# dv_spectrum_col.net
KiCad netlist of a schematic drawn in Altium Designer
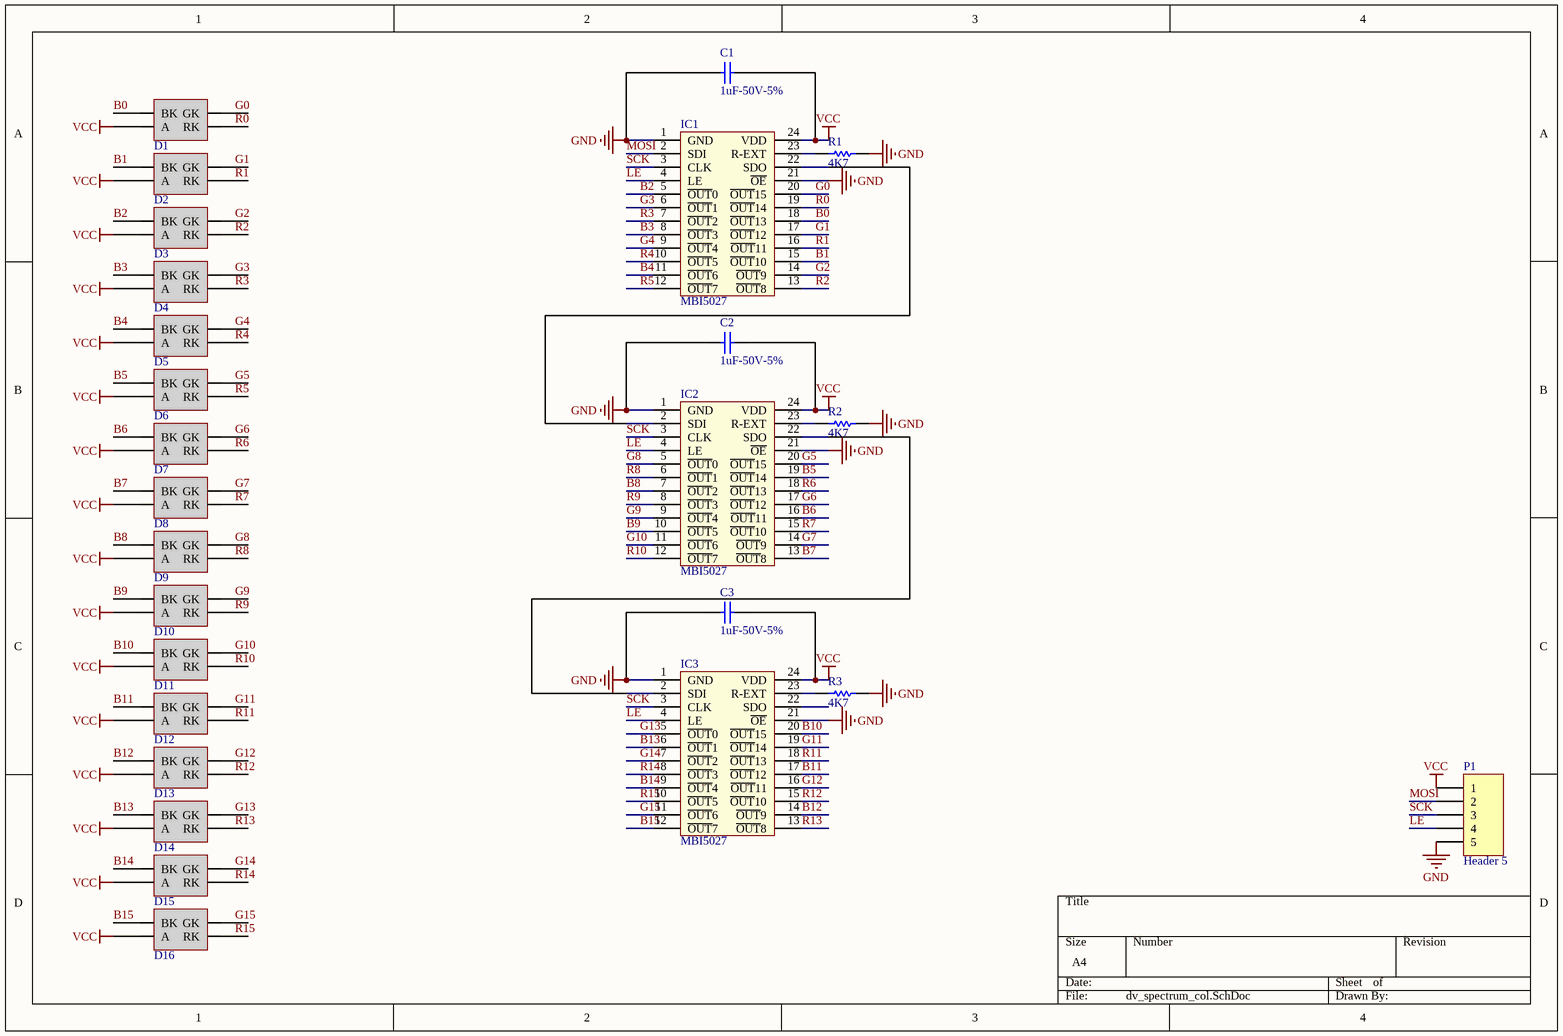
[diagram p0: dv_spectrum_col.SchDoc]

(export (version "E")
  (design (tool "Eeschema 10.0.6"))
  (components
    (comp (ref "C1")
      (value "1uF-50V-5%")
      (footprint "CAPC2012X135N")
      (description "CAP CER 15PF 50V 5% NPO 0603")
      (fields
        (field (name "MANUFACTURER") "Yageo")
        (field (name "DIGI-KEY PART NUMBER") "311-1060-1-ND")
        (field (name "PUBLISHER") "Altium Limited")
      )
      (libsource (lib "altium-import") (part "root_0_Cap_"))
    )
    (comp (ref "C2")
      (value "1uF-50V-5%")
      (footprint "CAPC2012X135N")
      (description "CAP CER 15PF 50V 5% NPO 0603")
      (fields
        (field (name "MANUFACTURER") "Yageo")
        (field (name "DIGI-KEY PART NUMBER") "311-1060-1-ND")
        (field (name "PUBLISHER") "Altium Limited")
      )
      (libsource (lib "altium-import") (part "root_0_Cap_"))
    )
    (comp (ref "C3")
      (value "1uF-50V-5%")
      (footprint "CAPC2012X135N")
      (description "CAP CER 15PF 50V 5% NPO 0603")
      (fields
        (field (name "MANUFACTURER") "Yageo")
        (field (name "DIGI-KEY PART NUMBER") "311-1060-1-ND")
        (field (name "PUBLISHER") "Altium Limited")
      )
      (libsource (lib "altium-import") (part "root_0_Cap_"))
    )
    (comp (ref "D1")
      (value "LED_RGB")
      (footprint "LED3528(1210)-RGB")
      (libsource (lib "PBL - Light Sources") (part "LED_RGB_1210"))
    )
    (comp (ref "D2")
      (value "LED_RGB")
      (footprint "LED3528(1210)-RGB")
      (libsource (lib "PBL - Light Sources") (part "LED_RGB_1210"))
    )
    (comp (ref "D3")
      (value "LED_RGB")
      (footprint "LED3528(1210)-RGB")
      (libsource (lib "PBL - Light Sources") (part "LED_RGB_1210"))
    )
    (comp (ref "D4")
      (value "LED_RGB")
      (footprint "LED3528(1210)-RGB")
      (libsource (lib "PBL - Light Sources") (part "LED_RGB_1210"))
    )
    (comp (ref "D5")
      (value "LED_RGB")
      (footprint "LED3528(1210)-RGB")
      (libsource (lib "PBL - Light Sources") (part "LED_RGB_1210"))
    )
    (comp (ref "D6")
      (value "LED_RGB")
      (footprint "LED3528(1210)-RGB")
      (libsource (lib "PBL - Light Sources") (part "LED_RGB_1210"))
    )
    (comp (ref "D7")
      (value "LED_RGB")
      (footprint "LED3528(1210)-RGB")
      (libsource (lib "PBL - Light Sources") (part "LED_RGB_1210"))
    )
    (comp (ref "D8")
      (value "LED_RGB")
      (footprint "LED3528(1210)-RGB")
      (libsource (lib "PBL - Light Sources") (part "LED_RGB_1210"))
    )
    (comp (ref "D9")
      (value "LED_RGB")
      (footprint "LED3528(1210)-RGB")
      (libsource (lib "PBL - Light Sources") (part "LED_RGB_1210"))
    )
    (comp (ref "D10")
      (value "LED_RGB")
      (footprint "LED3528(1210)-RGB")
      (libsource (lib "PBL - Light Sources") (part "LED_RGB_1210"))
    )
    (comp (ref "D11")
      (value "LED_RGB")
      (footprint "LED3528(1210)-RGB")
      (libsource (lib "PBL - Light Sources") (part "LED_RGB_1210"))
    )
    (comp (ref "D12")
      (value "LED_RGB")
      (footprint "LED3528(1210)-RGB")
      (libsource (lib "PBL - Light Sources") (part "LED_RGB_1210"))
    )
    (comp (ref "D13")
      (value "LED_RGB")
      (footprint "LED3528(1210)-RGB")
      (libsource (lib "PBL - Light Sources") (part "LED_RGB_1210"))
    )
    (comp (ref "D14")
      (value "LED_RGB")
      (footprint "LED3528(1210)-RGB")
      (libsource (lib "PBL - Light Sources") (part "LED_RGB_1210"))
    )
    (comp (ref "D15")
      (value "LED_RGB")
      (footprint "LED3528(1210)-RGB")
      (libsource (lib "PBL - Light Sources") (part "LED_RGB_1210"))
    )
    (comp (ref "D16")
      (value "LED_RGB")
      (footprint "LED3528(1210)-RGB")
      (libsource (lib "PBL - Light Sources") (part "LED_RGB_1210"))
    )
    (comp (ref "IC1")
      (value "MBI5027")
      (footprint "SSOP24")
      (description "16 bit Constant Current LED")
      (fields (field (name "CREAT BY") "VanDungEvn@Gmail.com"))
      (libsource (lib "syhaunguyen") (part "MBI5027"))
    )
    (comp (ref "IC2")
      (value "MBI5027")
      (footprint "SSOP24")
      (description "16 bit Constant Current LED")
      (fields (field (name "CREAT BY") "VanDungEvn@Gmail.com"))
      (libsource (lib "syhaunguyen") (part "MBI5027"))
    )
    (comp (ref "IC3")
      (value "MBI5027")
      (footprint "SSOP24")
      (description "16 bit Constant Current LED")
      (fields (field (name "CREAT BY") "VanDungEvn@Gmail.com"))
      (libsource (lib "syhaunguyen") (part "MBI5027"))
    )
    (comp (ref "P1")
      (value "Header 5")
      (footprint "HDR1X5")
      (description "Header, 5-Pin")
      (fields (field (name "PUBLISHER") "Altium Limited"))
      (libsource (lib "Miscellaneous Connectors") (part "Header 5"))
    )
    (comp (ref "R1")
      (value "4K7")
      (footprint "R0805")
      (description "Resistor")
      (fields (field (name "Comment") "Res1") (field (name "PUBLISHER") "Altium Limited"))
      (libsource (lib "Miscellaneous Devices") (part "Res1"))
    )
    (comp (ref "R2")
      (value "4K7")
      (footprint "R0805")
      (description "Resistor")
      (fields (field (name "Comment") "Res1") (field (name "PUBLISHER") "Altium Limited"))
      (libsource (lib "Miscellaneous Devices") (part "Res1"))
    )
    (comp (ref "R3")
      (value "4K7")
      (footprint "R0805")
      (description "Resistor")
      (fields (field (name "Comment") "Res1") (field (name "PUBLISHER") "Altium Limited"))
      (libsource (lib "Miscellaneous Devices") (part "Res1"))
    )
  )
  (nets
    (net (code "1") (name "/B0") (class "Default")
      (node (ref "D1") (pin "3") (pinfunction "BK_3") (pintype "passive"))
      (node (ref "IC1") (pin "18") (pinfunction "~{OUT}13_18") (pintype "passive"))
    )
    (net (code "2") (name "/B1") (class "Default")
      (node (ref "D2") (pin "3") (pinfunction "BK_3") (pintype "passive"))
      (node (ref "IC1") (pin "15") (pinfunction "~{OUT}10_15") (pintype "passive"))
    )
    (net (code "3") (name "/B2") (class "Default")
      (node (ref "D3") (pin "3") (pinfunction "BK_3") (pintype "passive"))
      (node (ref "IC1") (pin "5") (pinfunction "~{OUT}0_5") (pintype "passive"))
    )
    (net (code "4") (name "/B3") (class "Default")
      (node (ref "D4") (pin "3") (pinfunction "BK_3") (pintype "passive"))
      (node (ref "IC1") (pin "8") (pinfunction "~{OUT}3_8") (pintype "passive"))
    )
    (net (code "5") (name "/B4") (class "Default")
      (node (ref "D5") (pin "3") (pinfunction "BK_3") (pintype "passive"))
      (node (ref "IC1") (pin "11") (pinfunction "~{OUT}6_11") (pintype "passive"))
    )
    (net (code "6") (name "/B5") (class "Default")
      (node (ref "D6") (pin "3") (pinfunction "BK_3") (pintype "passive"))
      (node (ref "IC2") (pin "19") (pinfunction "~{OUT}14_19") (pintype "passive"))
    )
    (net (code "7") (name "/B6") (class "Default")
      (node (ref "D7") (pin "3") (pinfunction "BK_3") (pintype "passive"))
      (node (ref "IC2") (pin "16") (pinfunction "~{OUT}11_16") (pintype "passive"))
    )
    (net (code "8") (name "/B7") (class "Default")
      (node (ref "D8") (pin "3") (pinfunction "BK_3") (pintype "passive"))
      (node (ref "IC2") (pin "13") (pinfunction "~{OUT}8_13") (pintype "passive"))
    )
    (net (code "9") (name "/B8") (class "Default")
      (node (ref "D9") (pin "3") (pinfunction "BK_3") (pintype "passive"))
      (node (ref "IC2") (pin "7") (pinfunction "~{OUT}2_7") (pintype "passive"))
    )
    (net (code "10") (name "/B9") (class "Default")
      (node (ref "D10") (pin "3") (pinfunction "BK_3") (pintype "passive"))
      (node (ref "IC2") (pin "10") (pinfunction "~{OUT}5_10") (pintype "passive"))
    )
    (net (code "11") (name "/B10") (class "Default")
      (node (ref "D11") (pin "3") (pinfunction "BK_3") (pintype "passive"))
      (node (ref "IC3") (pin "20") (pinfunction "~{OUT}15_20") (pintype "passive"))
    )
    (net (code "12") (name "/B11") (class "Default")
      (node (ref "D12") (pin "3") (pinfunction "BK_3") (pintype "passive"))
      (node (ref "IC3") (pin "17") (pinfunction "~{OUT}12_17") (pintype "passive"))
    )
    (net (code "13") (name "/B12") (class "Default")
      (node (ref "D13") (pin "3") (pinfunction "BK_3") (pintype "passive"))
      (node (ref "IC3") (pin "14") (pinfunction "~{OUT}9_14") (pintype "passive"))
    )
    (net (code "14") (name "/B13") (class "Default")
      (node (ref "D14") (pin "3") (pinfunction "BK_3") (pintype "passive"))
      (node (ref "IC3") (pin "6") (pinfunction "~{OUT}1_6") (pintype "passive"))
    )
    (net (code "15") (name "/B14") (class "Default")
      (node (ref "D15") (pin "3") (pinfunction "BK_3") (pintype "passive"))
      (node (ref "IC3") (pin "9") (pinfunction "~{OUT}4_9") (pintype "passive"))
    )
    (net (code "16") (name "/B15") (class "Default")
      (node (ref "D16") (pin "3") (pinfunction "BK_3") (pintype "passive"))
      (node (ref "IC3") (pin "12") (pinfunction "~{OUT}7_12") (pintype "passive"))
    )
    (net (code "17") (name "/G0") (class "Default")
      (node (ref "D1") (pin "4") (pinfunction "GK_4") (pintype "passive"))
      (node (ref "IC1") (pin "20") (pinfunction "~{OUT}15_20") (pintype "passive"))
    )
    (net (code "18") (name "/G1") (class "Default")
      (node (ref "D2") (pin "4") (pinfunction "GK_4") (pintype "passive"))
      (node (ref "IC1") (pin "17") (pinfunction "~{OUT}12_17") (pintype "passive"))
    )
    (net (code "19") (name "/G2") (class "Default")
      (node (ref "D3") (pin "4") (pinfunction "GK_4") (pintype "passive"))
      (node (ref "IC1") (pin "14") (pinfunction "~{OUT}9_14") (pintype "passive"))
    )
    (net (code "20") (name "/G3") (class "Default")
      (node (ref "D4") (pin "4") (pinfunction "GK_4") (pintype "passive"))
      (node (ref "IC1") (pin "6") (pinfunction "~{OUT}1_6") (pintype "passive"))
    )
    (net (code "21") (name "/G4") (class "Default")
      (node (ref "D5") (pin "4") (pinfunction "GK_4") (pintype "passive"))
      (node (ref "IC1") (pin "9") (pinfunction "~{OUT}4_9") (pintype "passive"))
    )
    (net (code "22") (name "/G5") (class "Default")
      (node (ref "D6") (pin "4") (pinfunction "GK_4") (pintype "passive"))
      (node (ref "IC2") (pin "20") (pinfunction "~{OUT}15_20") (pintype "passive"))
    )
    (net (code "23") (name "/G6") (class "Default")
      (node (ref "D7") (pin "4") (pinfunction "GK_4") (pintype "passive"))
      (node (ref "IC2") (pin "17") (pinfunction "~{OUT}12_17") (pintype "passive"))
    )
    (net (code "24") (name "/G7") (class "Default")
      (node (ref "D8") (pin "4") (pinfunction "GK_4") (pintype "passive"))
      (node (ref "IC2") (pin "14") (pinfunction "~{OUT}9_14") (pintype "passive"))
    )
    (net (code "25") (name "/G8") (class "Default")
      (node (ref "D9") (pin "4") (pinfunction "GK_4") (pintype "passive"))
      (node (ref "IC2") (pin "5") (pinfunction "~{OUT}0_5") (pintype "passive"))
    )
    (net (code "26") (name "/G9") (class "Default")
      (node (ref "D10") (pin "4") (pinfunction "GK_4") (pintype "passive"))
      (node (ref "IC2") (pin "9") (pinfunction "~{OUT}4_9") (pintype "passive"))
    )
    (net (code "27") (name "/G10") (class "Default")
      (node (ref "D11") (pin "4") (pinfunction "GK_4") (pintype "passive"))
      (node (ref "IC2") (pin "11") (pinfunction "~{OUT}6_11") (pintype "passive"))
    )
    (net (code "28") (name "/G11") (class "Default")
      (node (ref "D12") (pin "4") (pinfunction "GK_4") (pintype "passive"))
      (node (ref "IC3") (pin "19") (pinfunction "~{OUT}14_19") (pintype "passive"))
    )
    (net (code "29") (name "/G12") (class "Default")
      (node (ref "D13") (pin "4") (pinfunction "GK_4") (pintype "passive"))
      (node (ref "IC3") (pin "16") (pinfunction "~{OUT}11_16") (pintype "passive"))
    )
    (net (code "30") (name "/G13") (class "Default")
      (node (ref "D14") (pin "4") (pinfunction "GK_4") (pintype "passive"))
      (node (ref "IC3") (pin "5") (pinfunction "~{OUT}0_5") (pintype "passive"))
    )
    (net (code "31") (name "/G14") (class "Default")
      (node (ref "D15") (pin "4") (pinfunction "GK_4") (pintype "passive"))
      (node (ref "IC3") (pin "7") (pinfunction "~{OUT}2_7") (pintype "passive"))
    )
    (net (code "32") (name "/G15") (class "Default")
      (node (ref "D16") (pin "4") (pinfunction "GK_4") (pintype "passive"))
      (node (ref "IC3") (pin "11") (pinfunction "~{OUT}6_11") (pintype "passive"))
    )
    (net (code "33") (name "/LE") (class "Default")
      (node (ref "IC1") (pin "4") (pinfunction "LE_4") (pintype "passive"))
      (node (ref "IC2") (pin "4") (pinfunction "LE_4") (pintype "passive"))
      (node (ref "IC3") (pin "4") (pinfunction "LE_4") (pintype "passive"))
      (node (ref "P1") (pin "4") (pinfunction "4_4") (pintype "passive"))
    )
    (net (code "34") (name "/MOSI") (class "Default")
      (node (ref "IC1") (pin "2") (pinfunction "SDI_2") (pintype "passive"))
      (node (ref "P1") (pin "2") (pinfunction "2_2") (pintype "passive"))
    )
    (net (code "35") (name "/R0") (class "Default")
      (node (ref "D1") (pin "1") (pinfunction "RK_1") (pintype "passive"))
      (node (ref "IC1") (pin "19") (pinfunction "~{OUT}14_19") (pintype "passive"))
    )
    (net (code "36") (name "/R1") (class "Default")
      (node (ref "D2") (pin "1") (pinfunction "RK_1") (pintype "passive"))
      (node (ref "IC1") (pin "16") (pinfunction "~{OUT}11_16") (pintype "passive"))
    )
    (net (code "37") (name "/R2") (class "Default")
      (node (ref "D3") (pin "1") (pinfunction "RK_1") (pintype "passive"))
      (node (ref "IC1") (pin "13") (pinfunction "~{OUT}8_13") (pintype "passive"))
    )
    (net (code "38") (name "/R3") (class "Default")
      (node (ref "D4") (pin "1") (pinfunction "RK_1") (pintype "passive"))
      (node (ref "IC1") (pin "7") (pinfunction "~{OUT}2_7") (pintype "passive"))
    )
    (net (code "39") (name "/R4") (class "Default")
      (node (ref "D5") (pin "1") (pinfunction "RK_1") (pintype "passive"))
      (node (ref "IC1") (pin "10") (pinfunction "~{OUT}5_10") (pintype "passive"))
    )
    (net (code "40") (name "/R5") (class "Default")
      (node (ref "D6") (pin "1") (pinfunction "RK_1") (pintype "passive"))
      (node (ref "IC1") (pin "12") (pinfunction "~{OUT}7_12") (pintype "passive"))
    )
    (net (code "41") (name "/R6") (class "Default")
      (node (ref "D7") (pin "1") (pinfunction "RK_1") (pintype "passive"))
      (node (ref "IC2") (pin "18") (pinfunction "~{OUT}13_18") (pintype "passive"))
    )
    (net (code "42") (name "/R7") (class "Default")
      (node (ref "D8") (pin "1") (pinfunction "RK_1") (pintype "passive"))
      (node (ref "IC2") (pin "15") (pinfunction "~{OUT}10_15") (pintype "passive"))
    )
    (net (code "43") (name "/R8") (class "Default")
      (node (ref "D9") (pin "1") (pinfunction "RK_1") (pintype "passive"))
      (node (ref "IC2") (pin "6") (pinfunction "~{OUT}1_6") (pintype "passive"))
    )
    (net (code "44") (name "/R9") (class "Default")
      (node (ref "D10") (pin "1") (pinfunction "RK_1") (pintype "passive"))
      (node (ref "IC2") (pin "8") (pinfunction "~{OUT}3_8") (pintype "passive"))
    )
    (net (code "45") (name "/R10") (class "Default")
      (node (ref "D11") (pin "1") (pinfunction "RK_1") (pintype "passive"))
      (node (ref "IC2") (pin "12") (pinfunction "~{OUT}7_12") (pintype "passive"))
    )
    (net (code "46") (name "/R11") (class "Default")
      (node (ref "D12") (pin "1") (pinfunction "RK_1") (pintype "passive"))
      (node (ref "IC3") (pin "18") (pinfunction "~{OUT}13_18") (pintype "passive"))
    )
    (net (code "47") (name "/R12") (class "Default")
      (node (ref "D13") (pin "1") (pinfunction "RK_1") (pintype "passive"))
      (node (ref "IC3") (pin "15") (pinfunction "~{OUT}10_15") (pintype "passive"))
    )
    (net (code "48") (name "/R13") (class "Default")
      (node (ref "D14") (pin "1") (pinfunction "RK_1") (pintype "passive"))
      (node (ref "IC3") (pin "13") (pinfunction "~{OUT}8_13") (pintype "passive"))
    )
    (net (code "49") (name "/R14") (class "Default")
      (node (ref "D15") (pin "1") (pinfunction "RK_1") (pintype "passive"))
      (node (ref "IC3") (pin "8") (pinfunction "~{OUT}3_8") (pintype "passive"))
    )
    (net (code "50") (name "/R15") (class "Default")
      (node (ref "D16") (pin "1") (pinfunction "RK_1") (pintype "passive"))
      (node (ref "IC3") (pin "10") (pinfunction "~{OUT}5_10") (pintype "passive"))
    )
    (net (code "51") (name "/SCK") (class "Default")
      (node (ref "IC1") (pin "3") (pinfunction "CLK_3") (pintype "passive"))
      (node (ref "IC2") (pin "3") (pinfunction "CLK_3") (pintype "passive"))
      (node (ref "IC3") (pin "3") (pinfunction "CLK_3") (pintype "passive"))
      (node (ref "P1") (pin "3") (pinfunction "3_3") (pintype "passive"))
    )
    (net (code "52") (name "GND") (class "Default")
      (node (ref "C1") (pin "1") (pinfunction "1_1") (pintype "passive"))
      (node (ref "C2") (pin "1") (pinfunction "1_1") (pintype "passive"))
      (node (ref "C3") (pin "1") (pinfunction "1_1") (pintype "passive"))
      (node (ref "IC1") (pin "1") (pinfunction "GND_1") (pintype "passive"))
      (node (ref "IC1") (pin "21") (pinfunction "~{OE}_21") (pintype "passive"))
      (node (ref "IC2") (pin "1") (pinfunction "GND_1") (pintype "passive"))
      (node (ref "IC2") (pin "21") (pinfunction "~{OE}_21") (pintype "passive"))
      (node (ref "IC3") (pin "1") (pinfunction "GND_1") (pintype "passive"))
      (node (ref "IC3") (pin "21") (pinfunction "~{OE}_21") (pintype "passive"))
      (node (ref "P1") (pin "5") (pinfunction "5_5") (pintype "passive"))
      (node (ref "R1") (pin "2") (pinfunction "2_2") (pintype "passive"))
      (node (ref "R2") (pin "2") (pinfunction "2_2") (pintype "passive"))
      (node (ref "R3") (pin "2") (pinfunction "2_2") (pintype "passive"))
    )
    (net (code "53") (name "Net-(IC1-R-EXT)") (class "Default")
      (node (ref "IC1") (pin "23") (pinfunction "R-EXT_23") (pintype "passive"))
      (node (ref "R1") (pin "1") (pinfunction "1_1") (pintype "passive"))
    )
    (net (code "54") (name "Net-(IC1-SDO)") (class "Default")
      (node (ref "IC1") (pin "22") (pinfunction "SDO_22") (pintype "passive"))
      (node (ref "IC2") (pin "2") (pinfunction "SDI_2") (pintype "passive"))
    )
    (net (code "55") (name "Net-(IC2-R-EXT)") (class "Default")
      (node (ref "IC2") (pin "23") (pinfunction "R-EXT_23") (pintype "passive"))
      (node (ref "R2") (pin "1") (pinfunction "1_1") (pintype "passive"))
    )
    (net (code "56") (name "Net-(IC2-SDO)") (class "Default")
      (node (ref "IC2") (pin "22") (pinfunction "SDO_22") (pintype "passive"))
      (node (ref "IC3") (pin "2") (pinfunction "SDI_2") (pintype "passive"))
    )
    (net (code "57") (name "Net-(IC3-R-EXT)") (class "Default")
      (node (ref "IC3") (pin "23") (pinfunction "R-EXT_23") (pintype "passive"))
      (node (ref "R3") (pin "1") (pinfunction "1_1") (pintype "passive"))
    )
    (net (code "58") (name "VCC") (class "Default")
      (node (ref "C1") (pin "2") (pinfunction "2_2") (pintype "passive"))
      (node (ref "C2") (pin "2") (pinfunction "2_2") (pintype "passive"))
      (node (ref "C3") (pin "2") (pinfunction "2_2") (pintype "passive"))
      (node (ref "D1") (pin "2") (pinfunction "A_2") (pintype "passive"))
      (node (ref "D10") (pin "2") (pinfunction "A_2") (pintype "passive"))
      (node (ref "D11") (pin "2") (pinfunction "A_2") (pintype "passive"))
      (node (ref "D12") (pin "2") (pinfunction "A_2") (pintype "passive"))
      (node (ref "D13") (pin "2") (pinfunction "A_2") (pintype "passive"))
      (node (ref "D14") (pin "2") (pinfunction "A_2") (pintype "passive"))
      (node (ref "D15") (pin "2") (pinfunction "A_2") (pintype "passive"))
      (node (ref "D16") (pin "2") (pinfunction "A_2") (pintype "passive"))
      (node (ref "D2") (pin "2") (pinfunction "A_2") (pintype "passive"))
      (node (ref "D3") (pin "2") (pinfunction "A_2") (pintype "passive"))
      (node (ref "D4") (pin "2") (pinfunction "A_2") (pintype "passive"))
      (node (ref "D5") (pin "2") (pinfunction "A_2") (pintype "passive"))
      (node (ref "D6") (pin "2") (pinfunction "A_2") (pintype "passive"))
      (node (ref "D7") (pin "2") (pinfunction "A_2") (pintype "passive"))
      (node (ref "D8") (pin "2") (pinfunction "A_2") (pintype "passive"))
      (node (ref "D9") (pin "2") (pinfunction "A_2") (pintype "passive"))
      (node (ref "IC1") (pin "24") (pinfunction "VDD_24") (pintype "passive"))
      (node (ref "IC2") (pin "24") (pinfunction "VDD_24") (pintype "passive"))
      (node (ref "IC3") (pin "24") (pinfunction "VDD_24") (pintype "passive"))
      (node (ref "P1") (pin "1") (pinfunction "1_1") (pintype "passive"))
    )
    (net (code "59") (name "unconnected-(IC3-SDO-Pad22)") (class "Default")
      (node (ref "IC3") (pin "22") (pinfunction "SDO_22") (pintype "passive"))
    )
  )
)
